# ChannelOutput-x2-opamp.net
KiCad netlist of a schematic drawn in EAGLE
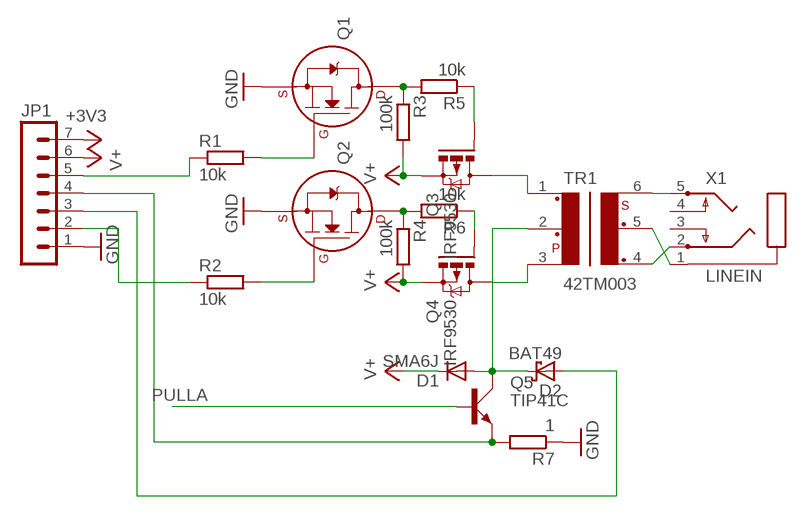
[diagram p0: schematic, sheet 1]
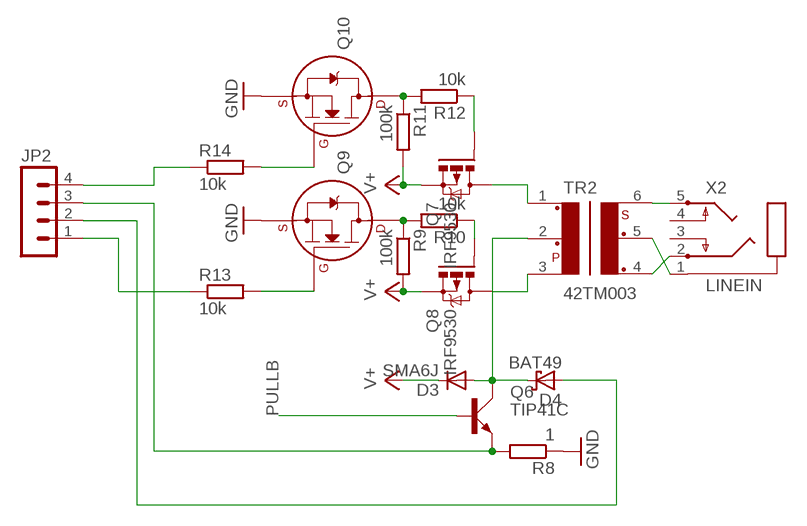
[diagram p1: schematic, sheet 2]
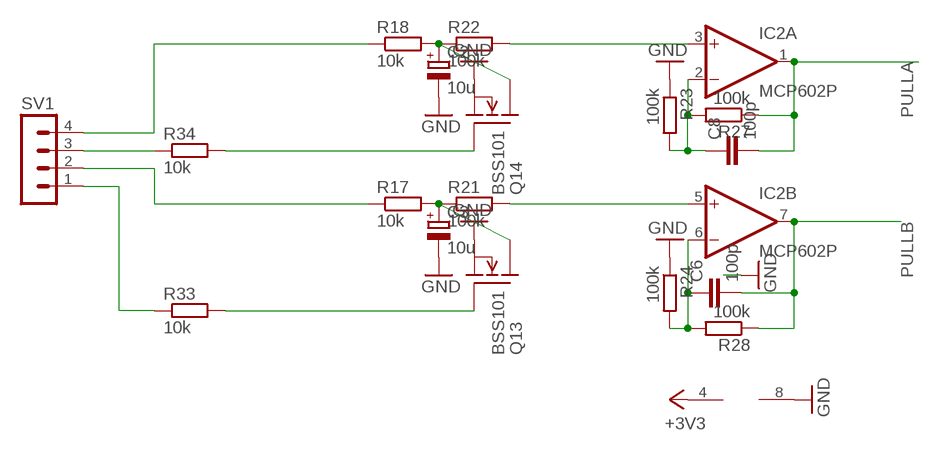
[diagram p2: schematic, sheet 3]

(export (version "E")
  (design (tool "Eeschema 10.0.6"))
  (components
    (comp (ref "D1")
      (value "SMA6J")
      (footprint "eagle-import:DO41-10")
      (libsource (lib "eagle-import") (part "1N4004"))
    )
    (comp (ref "D2")
      (value "BAT49")
      (footprint "eagle-import:DO41-10")
      (libsource (lib "eagle-import") (part "BAT49"))
    )
    (comp (ref "JP1")
      (value "MA07-1")
      (footprint "eagle-import:MA07-1")
      (libsource (lib "eagle-import") (part "MA07-1"))
    )
    (comp (ref "Q1")
      (value "2N7000_TO92")
      (footprint "eagle-import:TO-92")
      (libsource (lib "eagle-import") (part "2N700_TO920"))
    )
    (comp (ref "Q2")
      (value "2N7000_TO92")
      (footprint "eagle-import:TO-92")
      (libsource (lib "eagle-import") (part "2N700_TO920"))
    )
    (comp (ref "Q3")
      (value "IRF9530")
      (footprint "eagle-import:TO220BV")
      (libsource (lib "eagle-import") (part "IRF9530"))
    )
    (comp (ref "Q4")
      (value "IRF9530")
      (footprint "eagle-import:TO220BV")
      (libsource (lib "eagle-import") (part "IRF9530"))
    )
    (comp (ref "Q5")
      (value "TIP41C")
      (footprint "eagle-import:TO220AV")
      (libsource (lib "eagle-import") (part "TIP41C"))
    )
    (comp (ref "R1")
      (value "10k")
      (footprint "eagle-import:0207_2V")
      (libsource (lib "eagle-import") (part "R-EU_0207/2V"))
    )
    (comp (ref "R2")
      (value "10k")
      (footprint "eagle-import:0207_2V")
      (libsource (lib "eagle-import") (part "R-EU_0207/2V"))
    )
    (comp (ref "R3")
      (value "100k")
      (footprint "eagle-import:0204_5")
      (libsource (lib "eagle-import") (part "R-EU_0204/5"))
    )
    (comp (ref "R4")
      (value "100k")
      (footprint "eagle-import:0204_5")
      (libsource (lib "eagle-import") (part "R-EU_0204/5"))
    )
    (comp (ref "R5")
      (value "10k")
      (footprint "eagle-import:0207_2V")
      (libsource (lib "eagle-import") (part "R-EU_0207/2V"))
    )
    (comp (ref "R6")
      (value "10k")
      (footprint "eagle-import:0207_2V")
      (libsource (lib "eagle-import") (part "R-EU_0207/2V"))
    )
    (comp (ref "R7")
      (value "1")
      (footprint "eagle-import:0207_2V")
      (libsource (lib "eagle-import") (part "R-EU_0207/2V"))
    )
    (comp (ref "TR1")
      (value "42TM003")
      (footprint "eagle-import:42TM")
      (libsource (lib "eagle-import") (part "42T?M003"))
    )
    (comp (ref "X1")
      (value "LINEIN")
      (footprint "eagle-import:PG203J")
      (libsource (lib "eagle-import") (part "PG203J"))
    )
    (comp (ref "C2")
      (value "10u")
      (footprint "eagle-import:TT2D5")
      (libsource (lib "eagle-import") (part "CPOL-EUTT2D5"))
    )
    (comp (ref "C3")
      (value "10u")
      (footprint "eagle-import:TT2D5")
      (libsource (lib "eagle-import") (part "CPOL-EUTT2D5"))
    )
    (comp (ref "C6")
      (value "100p")
      (footprint "eagle-import:C025-024X044")
      (libsource (lib "eagle-import") (part "C-EU025-024X044"))
    )
    (comp (ref "C8")
      (value "100p")
      (footprint "eagle-import:C025-024X044")
      (libsource (lib "eagle-import") (part "C-EU025-024X044"))
    )
    (comp (ref "IC2")
      (value "MCP602P")
      (footprint "eagle-import:DIL08")
      (libsource (lib "eagle-import") (part "MCP602P"))
    )
    (comp (ref "Q13")
      (value "BSS101")
      (footprint "eagle-import:TO92")
      (libsource (lib "eagle-import") (part "BSS101"))
    )
    (comp (ref "Q14")
      (value "BSS101")
      (footprint "eagle-import:TO92")
      (libsource (lib "eagle-import") (part "BSS101"))
    )
    (comp (ref "R17")
      (value "10k")
      (footprint "eagle-import:0207_2V")
      (libsource (lib "eagle-import") (part "R-EU_0207/2V"))
    )
    (comp (ref "R18")
      (value "10k")
      (footprint "eagle-import:0207_2V")
      (libsource (lib "eagle-import") (part "R-EU_0207/2V"))
    )
    (comp (ref "R21")
      (value "100k")
      (footprint "eagle-import:0207_2V")
      (libsource (lib "eagle-import") (part "R-EU_0207/2V"))
    )
    (comp (ref "R22")
      (value "100k")
      (footprint "eagle-import:0207_2V")
      (libsource (lib "eagle-import") (part "R-EU_0207/2V"))
    )
    (comp (ref "R23")
      (value "100k")
      (footprint "eagle-import:0207_2V")
      (libsource (lib "eagle-import") (part "R-EU_0207/2V"))
    )
    (comp (ref "R24")
      (value "100k")
      (footprint "eagle-import:0207_2V")
      (libsource (lib "eagle-import") (part "R-EU_0207/2V"))
    )
    (comp (ref "R27")
      (value "100k")
      (footprint "eagle-import:0207_2V")
      (libsource (lib "eagle-import") (part "R-EU_0207/2V"))
    )
    (comp (ref "R28")
      (value "100k")
      (footprint "eagle-import:0207_2V")
      (libsource (lib "eagle-import") (part "R-EU_0207/2V"))
    )
    (comp (ref "R33")
      (value "10k")
      (footprint "eagle-import:0207_2V")
      (libsource (lib "eagle-import") (part "R-EU_0207/2V"))
    )
    (comp (ref "R34")
      (value "10k")
      (footprint "eagle-import:0207_2V")
      (libsource (lib "eagle-import") (part "R-EU_0207/2V"))
    )
    (comp (ref "SV1")
      (value "MA04-1")
      (footprint "eagle-import:MA04-1")
      (libsource (lib "eagle-import") (part "MA04-1"))
    )
    (comp (ref "D3")
      (value "SMA6J")
      (footprint "eagle-import:DO41-10")
      (libsource (lib "eagle-import") (part "1N4004"))
    )
    (comp (ref "D4")
      (value "BAT49")
      (footprint "eagle-import:DO41-10")
      (libsource (lib "eagle-import") (part "BAT49"))
    )
    (comp (ref "JP2")
      (value "MA04-1")
      (footprint "eagle-import:MA04-1")
      (libsource (lib "eagle-import") (part "MA04-1"))
    )
    (comp (ref "Q6")
      (value "TIP41C")
      (footprint "eagle-import:TO220AV")
      (libsource (lib "eagle-import") (part "TIP41C"))
    )
    (comp (ref "Q7")
      (value "IRF9530")
      (footprint "eagle-import:TO220BV")
      (libsource (lib "eagle-import") (part "IRF9530"))
    )
    (comp (ref "Q8")
      (value "IRF9530")
      (footprint "eagle-import:TO220BV")
      (libsource (lib "eagle-import") (part "IRF9530"))
    )
    (comp (ref "Q9")
      (value "2N7000_TO92")
      (footprint "eagle-import:TO-92")
      (libsource (lib "eagle-import") (part "2N700_TO920"))
    )
    (comp (ref "Q10")
      (value "2N7000_TO92")
      (footprint "eagle-import:TO-92")
      (libsource (lib "eagle-import") (part "2N700_TO920"))
    )
    (comp (ref "R8")
      (value "1")
      (footprint "eagle-import:0207_2V")
      (libsource (lib "eagle-import") (part "R-EU_0207/2V"))
    )
    (comp (ref "R9")
      (value "100k")
      (footprint "eagle-import:0204_5")
      (libsource (lib "eagle-import") (part "R-EU_0204/5"))
    )
    (comp (ref "R10")
      (value "10k")
      (footprint "eagle-import:0207_2V")
      (libsource (lib "eagle-import") (part "R-EU_0207/2V"))
    )
    (comp (ref "R11")
      (value "100k")
      (footprint "eagle-import:0204_5")
      (libsource (lib "eagle-import") (part "R-EU_0204/5"))
    )
    (comp (ref "R12")
      (value "10k")
      (footprint "eagle-import:0207_2V")
      (libsource (lib "eagle-import") (part "R-EU_0207/2V"))
    )
    (comp (ref "R13")
      (value "10k")
      (footprint "eagle-import:0207_2V")
      (libsource (lib "eagle-import") (part "R-EU_0207/2V"))
    )
    (comp (ref "R14")
      (value "10k")
      (footprint "eagle-import:0207_2V")
      (libsource (lib "eagle-import") (part "R-EU_0207/2V"))
    )
    (comp (ref "TR2")
      (value "42TM003")
      (footprint "eagle-import:42TM")
      (libsource (lib "eagle-import") (part "42T?M003"))
    )
    (comp (ref "X2")
      (value "LINEIN")
      (footprint "eagle-import:PG203J")
      (libsource (lib "eagle-import") (part "PG203J"))
    )
  )
  (nets
    (net (code "1") (name "+3V3") (class "Default")
      (node (ref "IC2") (pin "4") (pinfunction "V-_4") (pintype "power_in"))
      (node (ref "JP1") (pin "7") (pinfunction "7_7") (pintype "passive"))
    )
    (net (code "2") (name "GND") (class "Default")
      (node (ref "C2") (pin "-") (pinfunction "-_-") (pintype "passive"))
      (node (ref "C3") (pin "-") (pinfunction "-_-") (pintype "passive"))
      (node (ref "IC2") (pin "8") (pinfunction "V+_8") (pintype "power_in"))
      (node (ref "JP1") (pin "1") (pinfunction "1_1") (pintype "passive"))
      (node (ref "Q1") (pin "1") (pinfunction "S_1") (pintype "bidirectional"))
      (node (ref "Q10") (pin "1") (pinfunction "S_1") (pintype "bidirectional"))
      (node (ref "Q13") (pin "1") (pinfunction "S_1") (pintype "passive"))
      (node (ref "Q14") (pin "1") (pinfunction "S_1") (pintype "passive"))
      (node (ref "Q2") (pin "1") (pinfunction "S_1") (pintype "bidirectional"))
      (node (ref "Q9") (pin "1") (pinfunction "S_1") (pintype "bidirectional"))
      (node (ref "R23") (pin "1") (pinfunction "1_1") (pintype "passive"))
      (node (ref "R24") (pin "1") (pinfunction "1_1") (pintype "passive"))
      (node (ref "R7") (pin "1") (pinfunction "1_1") (pintype "passive"))
      (node (ref "R8") (pin "1") (pinfunction "1_1") (pintype "passive"))
    )
    (net (code "3") (name "Net-(D1-PadA)") (class "Default")
      (node (ref "D1") (pin "A") (pinfunction "A_A") (pintype "passive"))
      (node (ref "D2") (pin "C") (pinfunction "C_C") (pintype "passive"))
      (node (ref "Q5") (pin "C") (pinfunction "C_C") (pintype "passive"))
      (node (ref "TR1") (pin "2") (pinfunction "2_2") (pintype "passive"))
    )
    (net (code "4") (name "Net-(D2-PadA)") (class "Default")
      (node (ref "D2") (pin "A") (pinfunction "A_A") (pintype "passive"))
      (node (ref "JP1") (pin "3") (pinfunction "3_3") (pintype "passive"))
    )
    (net (code "5") (name "Net-(D3-PadA)") (class "Default")
      (node (ref "D3") (pin "A") (pinfunction "A_A") (pintype "passive"))
      (node (ref "D4") (pin "C") (pinfunction "C_C") (pintype "passive"))
      (node (ref "Q6") (pin "C") (pinfunction "C_C") (pintype "passive"))
      (node (ref "TR2") (pin "2") (pinfunction "2_2") (pintype "passive"))
    )
    (net (code "6") (name "Net-(D4-PadA)") (class "Default")
      (node (ref "D4") (pin "A") (pinfunction "A_A") (pintype "passive"))
      (node (ref "JP2") (pin "2") (pinfunction "2_2") (pintype "passive"))
    )
    (net (code "7") (name "Net-(IC2A-+IN)") (class "Default")
      (node (ref "IC2") (pin "3") (pinfunction "+IN_3") (pintype "input"))
      (node (ref "R22") (pin "2") (pinfunction "2_2") (pintype "passive"))
    )
    (net (code "8") (name "Net-(IC2A--IN)") (class "Default")
      (node (ref "C8") (pin "1") (pinfunction "1_1") (pintype "passive"))
      (node (ref "IC2") (pin "2") (pinfunction "-IN_2") (pintype "input"))
      (node (ref "R23") (pin "2") (pinfunction "2_2") (pintype "passive"))
      (node (ref "R27") (pin "2") (pinfunction "2_2") (pintype "passive"))
    )
    (net (code "9") (name "Net-(IC2B-+IN)") (class "Default")
      (node (ref "IC2") (pin "5") (pinfunction "+IN_5") (pintype "input"))
      (node (ref "R21") (pin "2") (pinfunction "2_2") (pintype "passive"))
    )
    (net (code "10") (name "Net-(IC2B--IN)") (class "Default")
      (node (ref "C6") (pin "1") (pinfunction "1_1") (pintype "passive"))
      (node (ref "IC2") (pin "6") (pinfunction "-IN_6") (pintype "input"))
      (node (ref "R24") (pin "2") (pinfunction "2_2") (pintype "passive"))
      (node (ref "R28") (pin "2") (pinfunction "2_2") (pintype "passive"))
    )
    (net (code "11") (name "Net-(JP1-Pad2)") (class "Default")
      (node (ref "JP1") (pin "2") (pinfunction "2_2") (pintype "passive"))
      (node (ref "R2") (pin "1") (pinfunction "1_1") (pintype "passive"))
    )
    (net (code "12") (name "Net-(JP1-Pad4)") (class "Default")
      (node (ref "JP1") (pin "4") (pinfunction "4_4") (pintype "passive"))
      (node (ref "Q5") (pin "E") (pinfunction "E_E") (pintype "passive"))
      (node (ref "R7") (pin "2") (pinfunction "2_2") (pintype "passive"))
    )
    (net (code "13") (name "Net-(JP1-Pad5)") (class "Default")
      (node (ref "JP1") (pin "5") (pinfunction "5_5") (pintype "passive"))
      (node (ref "R1") (pin "1") (pinfunction "1_1") (pintype "passive"))
    )
    (net (code "14") (name "Net-(JP2-Pad1)") (class "Default")
      (node (ref "JP2") (pin "1") (pinfunction "1_1") (pintype "passive"))
      (node (ref "R13") (pin "1") (pinfunction "1_1") (pintype "passive"))
    )
    (net (code "15") (name "Net-(JP2-Pad3)") (class "Default")
      (node (ref "JP2") (pin "3") (pinfunction "3_3") (pintype "passive"))
      (node (ref "Q6") (pin "E") (pinfunction "E_E") (pintype "passive"))
      (node (ref "R8") (pin "2") (pinfunction "2_2") (pintype "passive"))
    )
    (net (code "16") (name "Net-(JP2-Pad4)") (class "Default")
      (node (ref "JP2") (pin "4") (pinfunction "4_4") (pintype "passive"))
      (node (ref "R14") (pin "1") (pinfunction "1_1") (pintype "passive"))
    )
    (net (code "17") (name "Net-(Q1-D)") (class "Default")
      (node (ref "Q1") (pin "3") (pinfunction "D_3") (pintype "bidirectional"))
      (node (ref "R3") (pin "1") (pinfunction "1_1") (pintype "passive"))
      (node (ref "R5") (pin "2") (pinfunction "2_2") (pintype "passive"))
    )
    (net (code "18") (name "Net-(Q1-G)") (class "Default")
      (node (ref "Q1") (pin "2") (pinfunction "G_2") (pintype "tri_state"))
      (node (ref "R1") (pin "2") (pinfunction "2_2") (pintype "passive"))
    )
    (net (code "19") (name "Net-(Q2-D)") (class "Default")
      (node (ref "Q2") (pin "3") (pinfunction "D_3") (pintype "bidirectional"))
      (node (ref "R4") (pin "1") (pinfunction "1_1") (pintype "passive"))
      (node (ref "R6") (pin "2") (pinfunction "2_2") (pintype "passive"))
    )
    (net (code "20") (name "Net-(Q2-G)") (class "Default")
      (node (ref "Q2") (pin "2") (pinfunction "G_2") (pintype "tri_state"))
      (node (ref "R2") (pin "2") (pinfunction "2_2") (pintype "passive"))
    )
    (net (code "21") (name "Net-(Q3-PadD)") (class "Default")
      (node (ref "Q3") (pin "D") (pinfunction "D_D") (pintype "passive"))
      (node (ref "TR1") (pin "1") (pinfunction "1_1") (pintype "passive"))
    )
    (net (code "22") (name "Net-(Q3-PadG)") (class "Default")
      (node (ref "Q3") (pin "G") (pinfunction "G_G") (pintype "passive"))
      (node (ref "R5") (pin "1") (pinfunction "1_1") (pintype "passive"))
    )
    (net (code "23") (name "Net-(Q4-PadD)") (class "Default")
      (node (ref "Q4") (pin "D") (pinfunction "D_D") (pintype "passive"))
      (node (ref "TR1") (pin "3") (pinfunction "3_3") (pintype "passive"))
    )
    (net (code "24") (name "Net-(Q4-PadG)") (class "Default")
      (node (ref "Q4") (pin "G") (pinfunction "G_G") (pintype "passive"))
      (node (ref "R6") (pin "1") (pinfunction "1_1") (pintype "passive"))
    )
    (net (code "25") (name "Net-(Q7-PadD)") (class "Default")
      (node (ref "Q7") (pin "D") (pinfunction "D_D") (pintype "passive"))
      (node (ref "TR2") (pin "1") (pinfunction "1_1") (pintype "passive"))
    )
    (net (code "26") (name "Net-(Q7-PadG)") (class "Default")
      (node (ref "Q7") (pin "G") (pinfunction "G_G") (pintype "passive"))
      (node (ref "R12") (pin "1") (pinfunction "1_1") (pintype "passive"))
    )
    (net (code "27") (name "Net-(Q8-PadD)") (class "Default")
      (node (ref "Q8") (pin "D") (pinfunction "D_D") (pintype "passive"))
      (node (ref "TR2") (pin "3") (pinfunction "3_3") (pintype "passive"))
    )
    (net (code "28") (name "Net-(Q8-PadG)") (class "Default")
      (node (ref "Q8") (pin "G") (pinfunction "G_G") (pintype "passive"))
      (node (ref "R10") (pin "1") (pinfunction "1_1") (pintype "passive"))
    )
    (net (code "29") (name "Net-(Q9-D)") (class "Default")
      (node (ref "Q9") (pin "3") (pinfunction "D_3") (pintype "bidirectional"))
      (node (ref "R10") (pin "2") (pinfunction "2_2") (pintype "passive"))
      (node (ref "R9") (pin "1") (pinfunction "1_1") (pintype "passive"))
    )
    (net (code "30") (name "Net-(Q9-G)") (class "Default")
      (node (ref "Q9") (pin "2") (pinfunction "G_2") (pintype "tri_state"))
      (node (ref "R13") (pin "2") (pinfunction "2_2") (pintype "passive"))
    )
    (net (code "31") (name "Net-(Q10-D)") (class "Default")
      (node (ref "Q10") (pin "3") (pinfunction "D_3") (pintype "bidirectional"))
      (node (ref "R11") (pin "1") (pinfunction "1_1") (pintype "passive"))
      (node (ref "R12") (pin "2") (pinfunction "2_2") (pintype "passive"))
    )
    (net (code "32") (name "Net-(Q10-G)") (class "Default")
      (node (ref "Q10") (pin "2") (pinfunction "G_2") (pintype "tri_state"))
      (node (ref "R14") (pin "2") (pinfunction "2_2") (pintype "passive"))
    )
    (net (code "33") (name "Net-(Q13-D)") (class "Default")
      (node (ref "C3") (pin "+") (pinfunction "+_+") (pintype "passive"))
      (node (ref "Q13") (pin "3") (pinfunction "D_3") (pintype "passive"))
      (node (ref "R17") (pin "2") (pinfunction "2_2") (pintype "passive"))
      (node (ref "R21") (pin "1") (pinfunction "1_1") (pintype "passive"))
    )
    (net (code "34") (name "Net-(Q13-G)") (class "Default")
      (node (ref "Q13") (pin "2") (pinfunction "G_2") (pintype "passive"))
      (node (ref "R33") (pin "2") (pinfunction "2_2") (pintype "passive"))
    )
    (net (code "35") (name "Net-(Q14-D)") (class "Default")
      (node (ref "C2") (pin "+") (pinfunction "+_+") (pintype "passive"))
      (node (ref "Q14") (pin "3") (pinfunction "D_3") (pintype "passive"))
      (node (ref "R18") (pin "2") (pinfunction "2_2") (pintype "passive"))
      (node (ref "R22") (pin "1") (pinfunction "1_1") (pintype "passive"))
    )
    (net (code "36") (name "Net-(Q14-G)") (class "Default")
      (node (ref "Q14") (pin "2") (pinfunction "G_2") (pintype "passive"))
      (node (ref "R34") (pin "2") (pinfunction "2_2") (pintype "passive"))
    )
    (net (code "37") (name "Net-(R17-Pad1)") (class "Default")
      (node (ref "R17") (pin "1") (pinfunction "1_1") (pintype "passive"))
      (node (ref "SV1") (pin "2") (pinfunction "2_2") (pintype "passive"))
    )
    (net (code "38") (name "Net-(R18-Pad1)") (class "Default")
      (node (ref "R18") (pin "1") (pinfunction "1_1") (pintype "passive"))
      (node (ref "SV1") (pin "4") (pinfunction "4_4") (pintype "passive"))
    )
    (net (code "39") (name "Net-(R33-Pad1)") (class "Default")
      (node (ref "R33") (pin "1") (pinfunction "1_1") (pintype "passive"))
      (node (ref "SV1") (pin "1") (pinfunction "1_1") (pintype "passive"))
    )
    (net (code "40") (name "Net-(R34-Pad1)") (class "Default")
      (node (ref "R34") (pin "1") (pinfunction "1_1") (pintype "passive"))
      (node (ref "SV1") (pin "3") (pinfunction "3_3") (pintype "passive"))
    )
    (net (code "41") (name "Net-(TR1-Pad4)") (class "Default")
      (node (ref "TR1") (pin "4") (pinfunction "4_4") (pintype "passive"))
      (node (ref "X1") (pin "2") (pinfunction "2_2") (pintype "passive"))
    )
    (net (code "42") (name "Net-(TR1-Pad5)") (class "Default")
      (node (ref "TR1") (pin "5") (pinfunction "5_5") (pintype "passive"))
      (node (ref "X1") (pin "1") (pinfunction "1_1") (pintype "passive"))
    )
    (net (code "43") (name "Net-(TR1-Pad6)") (class "Default")
      (node (ref "TR1") (pin "6") (pinfunction "6_6") (pintype "passive"))
      (node (ref "X1") (pin "5") (pinfunction "5_5") (pintype "passive"))
    )
    (net (code "44") (name "Net-(TR2-Pad4)") (class "Default")
      (node (ref "TR2") (pin "4") (pinfunction "4_4") (pintype "passive"))
      (node (ref "X2") (pin "2") (pinfunction "2_2") (pintype "passive"))
    )
    (net (code "45") (name "Net-(TR2-Pad5)") (class "Default")
      (node (ref "TR2") (pin "5") (pinfunction "5_5") (pintype "passive"))
      (node (ref "X2") (pin "1") (pinfunction "1_1") (pintype "passive"))
    )
    (net (code "46") (name "Net-(TR2-Pad6)") (class "Default")
      (node (ref "TR2") (pin "6") (pinfunction "6_6") (pintype "passive"))
      (node (ref "X2") (pin "5") (pinfunction "5_5") (pintype "passive"))
    )
    (net (code "47") (name "PULLA") (class "Default")
      (node (ref "C8") (pin "2") (pinfunction "2_2") (pintype "passive"))
      (node (ref "IC2") (pin "1") (pinfunction "OUT_1") (pintype "output"))
      (node (ref "Q5") (pin "B") (pinfunction "B_B") (pintype "passive"))
      (node (ref "R27") (pin "1") (pinfunction "1_1") (pintype "passive"))
    )
    (net (code "48") (name "PULLB") (class "Default")
      (node (ref "C6") (pin "2") (pinfunction "2_2") (pintype "passive"))
      (node (ref "IC2") (pin "7") (pinfunction "OUT_7") (pintype "output"))
      (node (ref "Q6") (pin "B") (pinfunction "B_B") (pintype "passive"))
      (node (ref "R28") (pin "1") (pinfunction "1_1") (pintype "passive"))
    )
    (net (code "49") (name "V+") (class "Default")
      (node (ref "D1") (pin "C") (pinfunction "C_C") (pintype "passive"))
      (node (ref "D3") (pin "C") (pinfunction "C_C") (pintype "passive"))
      (node (ref "JP1") (pin "6") (pinfunction "6_6") (pintype "passive"))
      (node (ref "Q3") (pin "S") (pinfunction "S_S") (pintype "passive"))
      (node (ref "Q4") (pin "S") (pinfunction "S_S") (pintype "passive"))
      (node (ref "Q7") (pin "S") (pinfunction "S_S") (pintype "passive"))
      (node (ref "Q8") (pin "S") (pinfunction "S_S") (pintype "passive"))
      (node (ref "R11") (pin "2") (pinfunction "2_2") (pintype "passive"))
      (node (ref "R3") (pin "2") (pinfunction "2_2") (pintype "passive"))
      (node (ref "R4") (pin "2") (pinfunction "2_2") (pintype "passive"))
      (node (ref "R9") (pin "2") (pinfunction "2_2") (pintype "passive"))
    )
    (net (code "50") (name "unconnected-(X1-Pad3)") (class "Default")
      (node (ref "X1") (pin "3") (pinfunction "3_3") (pintype "passive"))
    )
    (net (code "51") (name "unconnected-(X1-Pad4)") (class "Default")
      (node (ref "X1") (pin "4") (pinfunction "4_4") (pintype "passive"))
    )
    (net (code "52") (name "unconnected-(X2-Pad3)") (class "Default")
      (node (ref "X2") (pin "3") (pinfunction "3_3") (pintype "passive"))
    )
    (net (code "53") (name "unconnected-(X2-Pad4)") (class "Default")
      (node (ref "X2") (pin "4") (pinfunction "4_4") (pintype "passive"))
    )
  )
)
